# 1U.net
KiCad netlist of a schematic drawn in Altium Designer
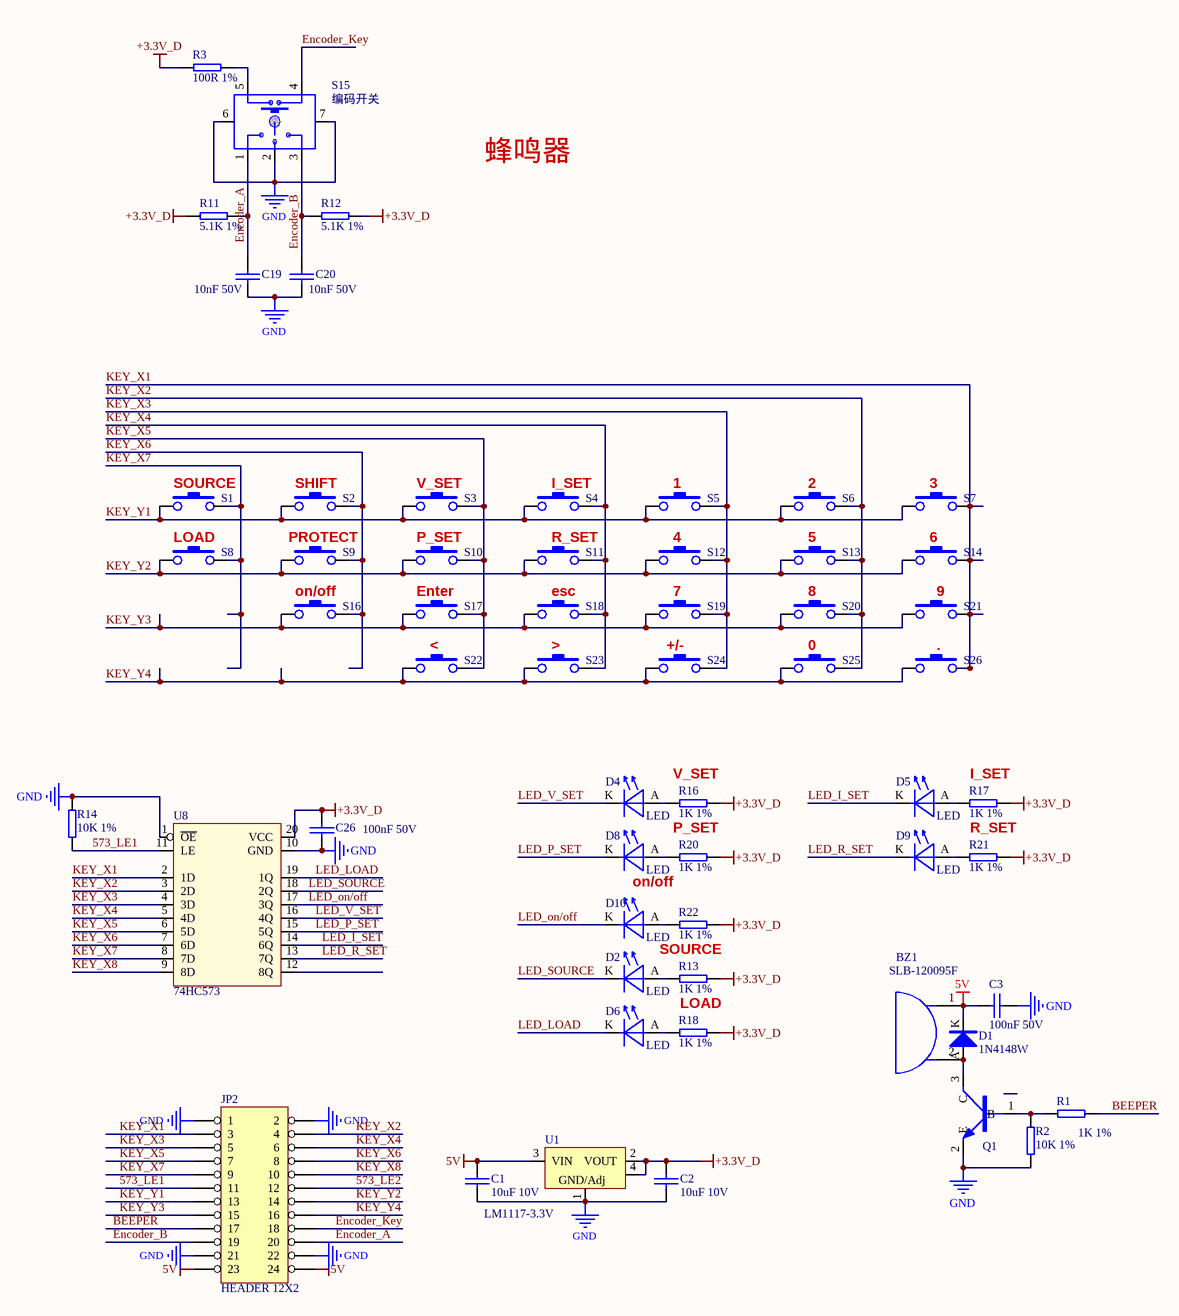
[diagram p0: 1U 按键.SchDoc]

(export (version "E")
  (design (tool "Eeschema 10.0.6"))
  (components
    (comp (ref "BZ1") (value "SLB-120095F") (footprint "BEEP12") (libsource (lib "原理图库") (part "Buzzer")))
    (comp (ref "C1")
      (value "10uF 10V")
      (footprint "C0603")
      (description "贴片电容")
      (libsource (lib "changyong") (part "10uF 0603 10V"))
    )
    (comp (ref "C2")
      (value "10uF 10V")
      (footprint "C0603")
      (description "贴片电容")
      (libsource (lib "changyong") (part "10uF 0603 10V"))
    )
    (comp (ref "C3")
      (value "100nF 50V")
      (footprint "C0603")
      (description "贴片电容")
      (libsource (lib "changyong") (part "100nF 0603 50V"))
    )
    (comp (ref "C19")
      (value "10nF 50V")
      (footprint "C0603")
      (description "贴片电容")
      (libsource (lib "changyong") (part "100nF 0603 50V"))
    )
    (comp (ref "C20")
      (value "10nF 50V")
      (footprint "C0603")
      (description "贴片电容")
      (libsource (lib "changyong") (part "100nF 0603 50V"))
    )
    (comp (ref "C26")
      (value "100nF 50V")
      (footprint "C0603")
      (description "贴片电容")
      (libsource (lib "changyong") (part "100nF 0603 50V"))
    )
    (comp (ref "D1")
      (value "1N4148W")
      (footprint "SOD-123")
      (description "二极管")
      (libsource (lib "changyong") (part "1N4148W SOD-123"))
    )
    (comp (ref "D2") (value "LED") (footprint "LED1206") (libsource (lib "changyongyuanjian") (part "LED")))
    (comp (ref "D4") (value "LED") (footprint "LED1206") (libsource (lib "changyongyuanjian") (part "LED")))
    (comp (ref "D5") (value "LED") (footprint "LED1206") (libsource (lib "changyongyuanjian") (part "LED")))
    (comp (ref "D6") (value "LED") (footprint "LED1206") (libsource (lib "changyongyuanjian") (part "LED")))
    (comp (ref "D8") (value "LED") (footprint "LED1206") (libsource (lib "changyongyuanjian") (part "LED")))
    (comp (ref "D9") (value "LED") (footprint "LED1206") (libsource (lib "changyongyuanjian") (part "LED")))
    (comp (ref "D10") (value "LED") (footprint "LED1206") (libsource (lib "changyongyuanjian") (part "LED")))
    (comp (ref "JP2")
      (value "HEADER 12X2")
      (footprint "FPC-SMD_P0.50-24P_H2.0")
      (libsource (lib "Miscellaneous Devices") (part "HEADER 12X2"))
    )
    (comp (ref "Q1")
      (value "S8050")
      (footprint "SOT-23")
      (description "NPN")
      (libsource (lib "changyong") (part "S8050 SOT-23"))
    )
    (comp (ref "R1")
      (value "1K 1%")
      (footprint "R0603")
      (description "贴片电阻")
      (libsource (lib "changyong") (part "1K 1% 0603"))
    )
    (comp (ref "R2")
      (value "10K 1%")
      (footprint "R0603")
      (description "贴片电阻")
      (libsource (lib "changyong") (part "10K 1% 0603"))
    )
    (comp (ref "R3")
      (value "100R 1%")
      (footprint "R0603")
      (description "贴片电阻")
      (libsource (lib "changyong") (part "100R 1% 0603"))
    )
    (comp (ref "R11")
      (value "5.1K 1%")
      (footprint "R0603")
      (description "贴片电阻")
      (libsource (lib "changyong") (part "5.1K 1% 0603"))
    )
    (comp (ref "R12")
      (value "5.1K 1%")
      (footprint "R0603")
      (description "贴片电阻")
      (libsource (lib "changyong") (part "5.1K 1% 0603"))
    )
    (comp (ref "R13")
      (value "1K 1%")
      (footprint "R0603")
      (description "贴片电阻")
      (libsource (lib "changyong") (part "1K 1% 0603"))
    )
    (comp (ref "R14")
      (value "10K 1%")
      (footprint "R0603")
      (description "贴片电阻")
      (libsource (lib "changyong") (part "10K 1% 0603"))
    )
    (comp (ref "R16")
      (value "1K 1%")
      (footprint "R0603")
      (description "贴片电阻")
      (libsource (lib "changyong") (part "1K 1% 0603"))
    )
    (comp (ref "R17")
      (value "1K 1%")
      (footprint "R0603")
      (description "贴片电阻")
      (libsource (lib "changyong") (part "1K 1% 0603"))
    )
    (comp (ref "R18")
      (value "1K 1%")
      (footprint "R0603")
      (description "贴片电阻")
      (libsource (lib "changyong") (part "1K 1% 0603"))
    )
    (comp (ref "R20")
      (value "1K 1%")
      (footprint "R0603")
      (description "贴片电阻")
      (libsource (lib "changyong") (part "1K 1% 0603"))
    )
    (comp (ref "R21")
      (value "1K 1%")
      (footprint "R0603")
      (description "贴片电阻")
      (libsource (lib "changyong") (part "1K 1% 0603"))
    )
    (comp (ref "R22")
      (value "1K 1%")
      (footprint "R0603")
      (description "贴片电阻")
      (libsource (lib "changyong") (part "1K 1% 0603"))
    )
    (comp (ref "S1")
      (value "SW-PB")
      (footprint "SW-SMD2")
      (libsource (lib "changyongyuanjian") (part "SW-PB"))
    )
    (comp (ref "S2")
      (value "SW-PB")
      (footprint "SW-SMD3")
      (libsource (lib "changyongyuanjian") (part "SW-PB"))
    )
    (comp (ref "S3")
      (value "SW-PB")
      (footprint "SW-SMD2")
      (libsource (lib "changyongyuanjian") (part "SW-PB"))
    )
    (comp (ref "S4")
      (value "SW-PB")
      (footprint "SW-SMD2")
      (libsource (lib "changyongyuanjian") (part "SW-PB"))
    )
    (comp (ref "S5")
      (value "SW-PB")
      (footprint "SW-SMD3")
      (libsource (lib "changyongyuanjian") (part "SW-PB"))
    )
    (comp (ref "S6")
      (value "SW-PB")
      (footprint "SW-SMD3")
      (libsource (lib "changyongyuanjian") (part "SW-PB"))
    )
    (comp (ref "S7")
      (value "SW-PB")
      (footprint "SW-SMD3")
      (libsource (lib "changyongyuanjian") (part "SW-PB"))
    )
    (comp (ref "S8")
      (value "SW-PB")
      (footprint "SW-SMD2")
      (libsource (lib "changyongyuanjian") (part "SW-PB"))
    )
    (comp (ref "S9")
      (value "SW-PB")
      (footprint "SW-SMD3")
      (libsource (lib "changyongyuanjian") (part "SW-PB"))
    )
    (comp (ref "S10")
      (value "SW-PB")
      (footprint "SW-SMD2")
      (libsource (lib "changyongyuanjian") (part "SW-PB"))
    )
    (comp (ref "S11")
      (value "SW-PB")
      (footprint "SW-SMD2")
      (libsource (lib "changyongyuanjian") (part "SW-PB"))
    )
    (comp (ref "S12")
      (value "SW-PB")
      (footprint "SW-SMD3")
      (libsource (lib "changyongyuanjian") (part "SW-PB"))
    )
    (comp (ref "S13")
      (value "SW-PB")
      (footprint "SW-SMD3")
      (libsource (lib "changyongyuanjian") (part "SW-PB"))
    )
    (comp (ref "S14")
      (value "SW-PB")
      (footprint "SW-SMD3")
      (libsource (lib "changyongyuanjian") (part "SW-PB"))
    )
    (comp (ref "S15") (value "编码开关") (footprint "EC-11") (libsource (lib "changyongyuanjian") (part "SW")))
    (comp (ref "S16")
      (value "SW-PB")
      (footprint "SW-SMD2")
      (libsource (lib "changyongyuanjian") (part "SW-PB"))
    )
    (comp (ref "S17")
      (value "SW-PB")
      (footprint "SW-SMD3")
      (libsource (lib "changyongyuanjian") (part "SW-PB"))
    )
    (comp (ref "S18")
      (value "SW-PB")
      (footprint "SW-SMD3")
      (libsource (lib "changyongyuanjian") (part "SW-PB"))
    )
    (comp (ref "S19")
      (value "SW-PB")
      (footprint "SW-SMD3")
      (libsource (lib "changyongyuanjian") (part "SW-PB"))
    )
    (comp (ref "S20")
      (value "SW-PB")
      (footprint "SW-SMD3")
      (libsource (lib "changyongyuanjian") (part "SW-PB"))
    )
    (comp (ref "S21")
      (value "SW-PB")
      (footprint "SW-SMD3")
      (libsource (lib "changyongyuanjian") (part "SW-PB"))
    )
    (comp (ref "S22")
      (value "SW-PB")
      (footprint "SW-SMD3")
      (libsource (lib "changyongyuanjian") (part "SW-PB"))
    )
    (comp (ref "S23")
      (value "SW-PB")
      (footprint "SW-SMD3")
      (libsource (lib "changyongyuanjian") (part "SW-PB"))
    )
    (comp (ref "S24")
      (value "SW-PB")
      (footprint "SW-SMD3")
      (libsource (lib "changyongyuanjian") (part "SW-PB"))
    )
    (comp (ref "S25")
      (value "SW-PB")
      (footprint "SW-SMD3")
      (libsource (lib "changyongyuanjian") (part "SW-PB"))
    )
    (comp (ref "S26")
      (value "SW-PB")
      (footprint "SW-SMD3")
      (libsource (lib "changyongyuanjian") (part "SW-PB"))
    )
    (comp (ref "U1")
      (value "LM1117-3.3V")
      (footprint "SOT-223")
      (description "线性稳压")
      (libsource (lib "changyong") (part "LM1117-3.3V SOT-223"))
    )
    (comp (ref "U8") (value "74HC573") (footprint "TSSOP-20") (libsource (lib "74") (part "74HC573")))
  )
  (nets
    (net (code "1") (name "+3.3V_D") (class "Default")
      (node (ref "C2") (pin "1") (pinfunction "1_1") (pintype "passive"))
      (node (ref "C26") (pin "1") (pinfunction "1_1") (pintype "passive"))
      (node (ref "R11") (pin "1") (pinfunction "1_1") (pintype "passive"))
      (node (ref "R12") (pin "2") (pinfunction "2_2") (pintype "passive"))
      (node (ref "R13") (pin "2") (pinfunction "2_2") (pintype "passive"))
      (node (ref "R16") (pin "2") (pinfunction "2_2") (pintype "passive"))
      (node (ref "R17") (pin "2") (pinfunction "2_2") (pintype "passive"))
      (node (ref "R18") (pin "2") (pinfunction "2_2") (pintype "passive"))
      (node (ref "R20") (pin "2") (pinfunction "2_2") (pintype "passive"))
      (node (ref "R21") (pin "2") (pinfunction "2_2") (pintype "passive"))
      (node (ref "R22") (pin "2") (pinfunction "2_2") (pintype "passive"))
      (node (ref "R3") (pin "1") (pinfunction "1_1") (pintype "passive"))
      (node (ref "U1") (pin "2") (pinfunction "VOUT_2") (pintype "passive"))
      (node (ref "U1") (pin "4") (pintype "passive"))
      (node (ref "U8") (pin "20") (pinfunction "VCC_20") (pintype "power_in"))
    )
    (net (code "2") (name "/573_LE1") (class "Default")
      (node (ref "JP2") (pin "11") (pinfunction "11_11") (pintype "passive"))
      (node (ref "R14") (pin "1") (pinfunction "1_1") (pintype "passive"))
      (node (ref "U8") (pin "11") (pinfunction "LE_11") (pintype "power_in"))
    )
    (net (code "3") (name "/573_LE2") (class "Default")
      (node (ref "JP2") (pin "12") (pinfunction "12_12") (pintype "passive"))
    )
    (net (code "4") (name "/BEEPER") (class "Default")
      (node (ref "JP2") (pin "17") (pinfunction "17_17") (pintype "passive"))
      (node (ref "R1") (pin "2") (pinfunction "2_2") (pintype "passive"))
    )
    (net (code "5") (name "/Encoder_A") (class "Default")
      (node (ref "C19") (pin "2") (pinfunction "2_2") (pintype "passive"))
      (node (ref "JP2") (pin "20") (pinfunction "20_20") (pintype "passive"))
      (node (ref "R11") (pin "2") (pinfunction "2_2") (pintype "passive"))
      (node (ref "S15") (pin "1") (pinfunction "1_1") (pintype "passive"))
    )
    (net (code "6") (name "/Encoder_B") (class "Default")
      (node (ref "C20") (pin "2") (pinfunction "2_2") (pintype "passive"))
      (node (ref "JP2") (pin "19") (pinfunction "19_19") (pintype "passive"))
      (node (ref "R12") (pin "1") (pinfunction "1_1") (pintype "passive"))
      (node (ref "S15") (pin "3") (pinfunction "3_3") (pintype "passive"))
    )
    (net (code "7") (name "/Encoder_Key") (class "Default")
      (node (ref "JP2") (pin "18") (pinfunction "18_18") (pintype "passive"))
      (node (ref "S15") (pin "4") (pinfunction "4_4") (pintype "passive"))
    )
    (net (code "8") (name "/KEY_X1") (class "Default")
      (node (ref "JP2") (pin "3") (pinfunction "3_3") (pintype "passive"))
      (node (ref "S14") (pin "2") (pinfunction "2_2") (pintype "passive"))
      (node (ref "S21") (pin "2") (pinfunction "2_2") (pintype "passive"))
      (node (ref "S26") (pin "2") (pinfunction "2_2") (pintype "passive"))
      (node (ref "S7") (pin "2") (pinfunction "2_2") (pintype "passive"))
      (node (ref "U8") (pin "2") (pinfunction "1D_2") (pintype "power_in"))
    )
    (net (code "9") (name "/KEY_X2") (class "Default")
      (node (ref "JP2") (pin "4") (pinfunction "4_4") (pintype "passive"))
      (node (ref "S13") (pin "2") (pinfunction "2_2") (pintype "passive"))
      (node (ref "S20") (pin "2") (pinfunction "2_2") (pintype "passive"))
      (node (ref "S25") (pin "2") (pinfunction "2_2") (pintype "passive"))
      (node (ref "S6") (pin "2") (pinfunction "2_2") (pintype "passive"))
      (node (ref "U8") (pin "3") (pinfunction "2D_3") (pintype "power_in"))
    )
    (net (code "10") (name "/KEY_X3") (class "Default")
      (node (ref "JP2") (pin "5") (pinfunction "5_5") (pintype "passive"))
      (node (ref "S12") (pin "2") (pinfunction "2_2") (pintype "passive"))
      (node (ref "S19") (pin "2") (pinfunction "2_2") (pintype "passive"))
      (node (ref "S24") (pin "2") (pinfunction "2_2") (pintype "passive"))
      (node (ref "S5") (pin "2") (pinfunction "2_2") (pintype "passive"))
      (node (ref "U8") (pin "4") (pinfunction "3D_4") (pintype "power_in"))
    )
    (net (code "11") (name "/KEY_X4") (class "Default")
      (node (ref "JP2") (pin "6") (pinfunction "6_6") (pintype "passive"))
      (node (ref "S11") (pin "2") (pinfunction "2_2") (pintype "passive"))
      (node (ref "S18") (pin "2") (pinfunction "2_2") (pintype "passive"))
      (node (ref "S23") (pin "2") (pinfunction "2_2") (pintype "passive"))
      (node (ref "S4") (pin "2") (pinfunction "2_2") (pintype "passive"))
      (node (ref "U8") (pin "5") (pinfunction "4D_5") (pintype "power_in"))
    )
    (net (code "12") (name "/KEY_X5") (class "Default")
      (node (ref "JP2") (pin "7") (pinfunction "7_7") (pintype "passive"))
      (node (ref "S10") (pin "2") (pinfunction "2_2") (pintype "passive"))
      (node (ref "S17") (pin "2") (pinfunction "2_2") (pintype "passive"))
      (node (ref "S22") (pin "2") (pinfunction "2_2") (pintype "passive"))
      (node (ref "S3") (pin "2") (pinfunction "2_2") (pintype "passive"))
      (node (ref "U8") (pin "6") (pinfunction "5D_6") (pintype "power_in"))
    )
    (net (code "13") (name "/KEY_X6") (class "Default")
      (node (ref "JP2") (pin "8") (pinfunction "8_8") (pintype "passive"))
      (node (ref "S16") (pin "2") (pinfunction "2_2") (pintype "passive"))
      (node (ref "S2") (pin "2") (pinfunction "2_2") (pintype "passive"))
      (node (ref "S9") (pin "2") (pinfunction "2_2") (pintype "passive"))
      (node (ref "U8") (pin "7") (pinfunction "6D_7") (pintype "power_in"))
    )
    (net (code "14") (name "/KEY_X7") (class "Default")
      (node (ref "JP2") (pin "9") (pinfunction "9_9") (pintype "passive"))
      (node (ref "S1") (pin "2") (pinfunction "2_2") (pintype "passive"))
      (node (ref "S8") (pin "2") (pinfunction "2_2") (pintype "passive"))
      (node (ref "U8") (pin "8") (pinfunction "7D_8") (pintype "power_in"))
    )
    (net (code "15") (name "/KEY_X8") (class "Default")
      (node (ref "JP2") (pin "10") (pinfunction "10_10") (pintype "passive"))
      (node (ref "U8") (pin "9") (pinfunction "8D_9") (pintype "power_in"))
    )
    (net (code "16") (name "/KEY_Y1") (class "Default")
      (node (ref "JP2") (pin "13") (pinfunction "13_13") (pintype "passive"))
      (node (ref "S1") (pin "1") (pinfunction "1_1") (pintype "passive"))
      (node (ref "S2") (pin "1") (pinfunction "1_1") (pintype "passive"))
      (node (ref "S3") (pin "1") (pinfunction "1_1") (pintype "passive"))
      (node (ref "S4") (pin "1") (pinfunction "1_1") (pintype "passive"))
      (node (ref "S5") (pin "1") (pinfunction "1_1") (pintype "passive"))
      (node (ref "S6") (pin "1") (pinfunction "1_1") (pintype "passive"))
      (node (ref "S7") (pin "1") (pinfunction "1_1") (pintype "passive"))
    )
    (net (code "17") (name "/KEY_Y2") (class "Default")
      (node (ref "JP2") (pin "14") (pinfunction "14_14") (pintype "passive"))
      (node (ref "S10") (pin "1") (pinfunction "1_1") (pintype "passive"))
      (node (ref "S11") (pin "1") (pinfunction "1_1") (pintype "passive"))
      (node (ref "S12") (pin "1") (pinfunction "1_1") (pintype "passive"))
      (node (ref "S13") (pin "1") (pinfunction "1_1") (pintype "passive"))
      (node (ref "S14") (pin "1") (pinfunction "1_1") (pintype "passive"))
      (node (ref "S8") (pin "1") (pinfunction "1_1") (pintype "passive"))
      (node (ref "S9") (pin "1") (pinfunction "1_1") (pintype "passive"))
    )
    (net (code "18") (name "/KEY_Y3") (class "Default")
      (node (ref "JP2") (pin "15") (pinfunction "15_15") (pintype "passive"))
      (node (ref "S16") (pin "1") (pinfunction "1_1") (pintype "passive"))
      (node (ref "S17") (pin "1") (pinfunction "1_1") (pintype "passive"))
      (node (ref "S18") (pin "1") (pinfunction "1_1") (pintype "passive"))
      (node (ref "S19") (pin "1") (pinfunction "1_1") (pintype "passive"))
      (node (ref "S20") (pin "1") (pinfunction "1_1") (pintype "passive"))
      (node (ref "S21") (pin "1") (pinfunction "1_1") (pintype "passive"))
    )
    (net (code "19") (name "/KEY_Y4") (class "Default")
      (node (ref "JP2") (pin "16") (pinfunction "16_16") (pintype "passive"))
      (node (ref "S22") (pin "1") (pinfunction "1_1") (pintype "passive"))
      (node (ref "S23") (pin "1") (pinfunction "1_1") (pintype "passive"))
      (node (ref "S24") (pin "1") (pinfunction "1_1") (pintype "passive"))
      (node (ref "S25") (pin "1") (pinfunction "1_1") (pintype "passive"))
      (node (ref "S26") (pin "1") (pinfunction "1_1") (pintype "passive"))
    )
    (net (code "20") (name "/LED_I_SET") (class "Default")
      (node (ref "D5") (pin "K") (pinfunction "K_K") (pintype "passive"))
      (node (ref "U8") (pin "14") (pinfunction "6Q_14") (pintype "power_in"))
    )
    (net (code "21") (name "/LED_LOAD") (class "Default")
      (node (ref "D6") (pin "K") (pinfunction "K_K") (pintype "passive"))
      (node (ref "U8") (pin "19") (pinfunction "1Q_19") (pintype "power_in"))
    )
    (net (code "22") (name "/LED_P_SET") (class "Default")
      (node (ref "D8") (pin "K") (pinfunction "K_K") (pintype "passive"))
      (node (ref "U8") (pin "15") (pinfunction "5Q_15") (pintype "power_in"))
    )
    (net (code "23") (name "/LED_R_SET") (class "Default")
      (node (ref "D9") (pin "K") (pinfunction "K_K") (pintype "passive"))
      (node (ref "U8") (pin "13") (pinfunction "7Q_13") (pintype "power_in"))
    )
    (net (code "24") (name "/LED_SOURCE") (class "Default")
      (node (ref "D2") (pin "K") (pinfunction "K_K") (pintype "passive"))
      (node (ref "U8") (pin "18") (pinfunction "2Q_18") (pintype "power_in"))
    )
    (net (code "25") (name "/LED_V_SET") (class "Default")
      (node (ref "D4") (pin "K") (pinfunction "K_K") (pintype "passive"))
      (node (ref "U8") (pin "16") (pinfunction "4Q_16") (pintype "power_in"))
    )
    (net (code "26") (name "/LED_on{slash}off") (class "Default")
      (node (ref "D10") (pin "K") (pinfunction "K_K") (pintype "passive"))
      (node (ref "U8") (pin "17") (pinfunction "3Q_17") (pintype "power_in"))
    )
    (net (code "27") (name "5V") (class "Default")
      (node (ref "BZ1") (pin "1") (pinfunction "1_1") (pintype "passive"))
      (node (ref "C1") (pin "1") (pinfunction "1_1") (pintype "passive"))
      (node (ref "C3") (pin "1") (pinfunction "1_1") (pintype "passive"))
      (node (ref "D1") (pin "K") (pinfunction "K_K") (pintype "passive"))
      (node (ref "JP2") (pin "23") (pinfunction "23_23") (pintype "passive"))
      (node (ref "JP2") (pin "24") (pinfunction "24_24") (pintype "passive"))
      (node (ref "U1") (pin "3") (pinfunction "VIN_3") (pintype "passive"))
    )
    (net (code "28") (name "GND") (class "Default")
      (node (ref "C1") (pin "2") (pinfunction "2_2") (pintype "passive"))
      (node (ref "C19") (pin "1") (pinfunction "1_1") (pintype "passive"))
      (node (ref "C2") (pin "2") (pinfunction "2_2") (pintype "passive"))
      (node (ref "C20") (pin "1") (pinfunction "1_1") (pintype "passive"))
      (node (ref "C26") (pin "2") (pinfunction "2_2") (pintype "passive"))
      (node (ref "C3") (pin "2") (pinfunction "2_2") (pintype "passive"))
      (node (ref "JP2") (pin "1") (pinfunction "1_1") (pintype "passive"))
      (node (ref "JP2") (pin "2") (pinfunction "2_2") (pintype "passive"))
      (node (ref "JP2") (pin "21") (pinfunction "21_21") (pintype "passive"))
      (node (ref "JP2") (pin "22") (pinfunction "22_22") (pintype "passive"))
      (node (ref "Q1") (pin "2") (pinfunction "E_2") (pintype "passive"))
      (node (ref "R14") (pin "2") (pinfunction "2_2") (pintype "passive"))
      (node (ref "R2") (pin "1") (pinfunction "1_1") (pintype "passive"))
      (node (ref "S15") (pin "2") (pinfunction "2_2") (pintype "passive"))
      (node (ref "S15") (pin "6") (pinfunction "6_6") (pintype "passive"))
      (node (ref "S15") (pin "7") (pinfunction "7_7") (pintype "passive"))
      (node (ref "U1") (pin "1") (pinfunction "GND/Adj_1") (pintype "passive"))
      (node (ref "U8") (pin "1") (pinfunction "~{OE}_1") (pintype "power_in"))
      (node (ref "U8") (pin "10") (pinfunction "GND_10") (pintype "power_in"))
    )
    (net (code "29") (name "Net-(D2-PadA)") (class "Default")
      (node (ref "D2") (pin "A") (pinfunction "A_A") (pintype "passive"))
      (node (ref "R13") (pin "1") (pinfunction "1_1") (pintype "passive"))
    )
    (net (code "30") (name "Net-(D4-PadA)") (class "Default")
      (node (ref "D4") (pin "A") (pinfunction "A_A") (pintype "passive"))
      (node (ref "R16") (pin "1") (pinfunction "1_1") (pintype "passive"))
    )
    (net (code "31") (name "Net-(D5-PadA)") (class "Default")
      (node (ref "D5") (pin "A") (pinfunction "A_A") (pintype "passive"))
      (node (ref "R17") (pin "1") (pinfunction "1_1") (pintype "passive"))
    )
    (net (code "32") (name "Net-(D6-PadA)") (class "Default")
      (node (ref "D6") (pin "A") (pinfunction "A_A") (pintype "passive"))
      (node (ref "R18") (pin "1") (pinfunction "1_1") (pintype "passive"))
    )
    (net (code "33") (name "Net-(D8-PadA)") (class "Default")
      (node (ref "D8") (pin "A") (pinfunction "A_A") (pintype "passive"))
      (node (ref "R20") (pin "1") (pinfunction "1_1") (pintype "passive"))
    )
    (net (code "34") (name "Net-(D9-PadA)") (class "Default")
      (node (ref "D9") (pin "A") (pinfunction "A_A") (pintype "passive"))
      (node (ref "R21") (pin "1") (pinfunction "1_1") (pintype "passive"))
    )
    (net (code "35") (name "Net-(D10-PadA)") (class "Default")
      (node (ref "D10") (pin "A") (pinfunction "A_A") (pintype "passive"))
      (node (ref "R22") (pin "1") (pinfunction "1_1") (pintype "passive"))
    )
    (net (code "36") (name "Net-(Q1-B)") (class "Default")
      (node (ref "Q1") (pin "1") (pinfunction "B_1") (pintype "passive"))
      (node (ref "R1") (pin "1") (pinfunction "1_1") (pintype "passive"))
      (node (ref "R2") (pin "2") (pinfunction "2_2") (pintype "passive"))
    )
    (net (code "37") (name "Net-(Q1-C)") (class "Default")
      (node (ref "BZ1") (pin "2") (pinfunction "2_2") (pintype "passive"))
      (node (ref "D1") (pin "A") (pinfunction "A_A") (pintype "passive"))
      (node (ref "Q1") (pin "3") (pinfunction "C_3") (pintype "passive"))
    )
    (net (code "38") (name "Net-(R3-Pad2)") (class "Default")
      (node (ref "R3") (pin "2") (pinfunction "2_2") (pintype "passive"))
      (node (ref "S15") (pin "5") (pinfunction "5_5") (pintype "passive"))
    )
    (net (code "39") (name "unconnected-(U8-8Q-Pad12)") (class "Default")
      (node (ref "U8") (pin "12") (pinfunction "8Q_12") (pintype "power_in"))
    )
  )
)
